# ina.net
KiCad netlist of a schematic drawn in Altium Designer
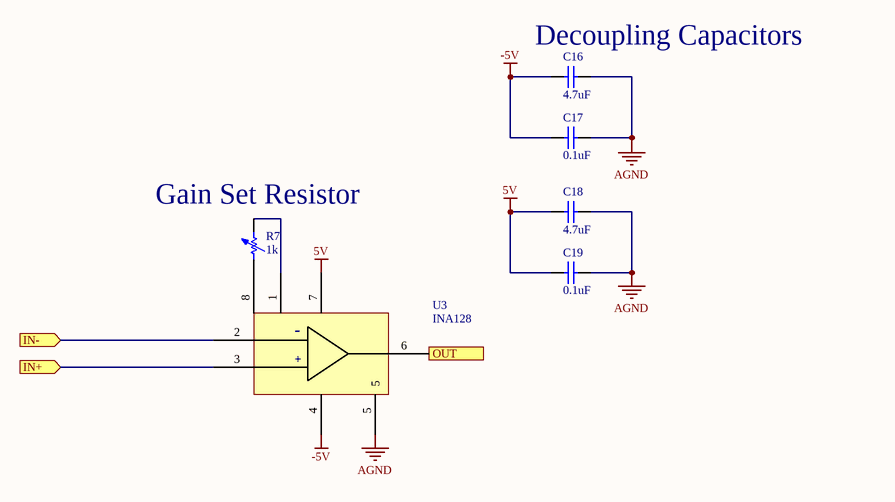
[diagram p0: ina.SchDoc]

(export (version "E")
  (design (tool "Eeschema 10.0.6"))
  (components
    (comp (ref "C16")
      (value "4.7uF")
      (footprint "0402_Cap")
      (description "Capacitor, 4.7uF, 0805")
      (libsource (lib "Arturo_Approved") (part "CL21A475KAQNNNE"))
    )
    (comp (ref "C17")
      (value "0.1uF")
      (footprint "0402_Cap")
      (description "Capacitor, 0.1uF, 0805")
      (libsource (lib "Arturo_Approved") (part "CL21B104KACNNNC"))
    )
    (comp (ref "C18")
      (value "4.7uF")
      (footprint "0402_Cap")
      (description "Capacitor, 4.7uF, 0805")
      (libsource (lib "Arturo_Approved") (part "CL21A475KAQNNNE"))
    )
    (comp (ref "C19")
      (value "0.1uF")
      (footprint "0402_Cap")
      (description "Capacitor, 0.1uF, 0805")
      (libsource (lib "Arturo_Approved") (part "CL21B104KACNNNC"))
    )
    (comp (ref "R7")
      (value "1k")
      (footprint "TRIMRES")
      (description "Variable resistor 1k")
      (libsource (lib "Arturo_Approved") (part "PV36W102C01B00_RES"))
    )
    (comp (ref "U3")
      (value "INA128")
      (footprint "SOIC_8")
      (description "Instrumentation Amp, Generic")
      (libsource (lib "Arturo_Approved") (part "INA128UA/2K5"))
    )
  )
  (nets
    (net (code "1") (name "-5V") (class "Default")
      (node (ref "C16") (pin "1") (pinfunction "1_1") (pintype "passive"))
      (node (ref "C17") (pin "1") (pinfunction "1_1") (pintype "passive"))
      (node (ref "U3") (pin "4") (pintype "passive"))
    )
    (net (code "2") (name "/IN+") (class "Default") (node (ref "U3") (pin "3") (pintype "passive")))
    (net (code "3") (name "/IN-") (class "Default") (node (ref "U3") (pin "2") (pintype "passive")))
    (net (code "4") (name "/OUT") (class "Default") (node (ref "U3") (pin "6") (pintype "passive")))
    (net (code "5") (name "5V") (class "Default")
      (node (ref "C18") (pin "1") (pinfunction "1_1") (pintype "passive"))
      (node (ref "C19") (pin "1") (pinfunction "1_1") (pintype "passive"))
      (node (ref "U3") (pin "7") (pintype "passive"))
    )
    (net (code "6") (name "AGND") (class "Default")
      (node (ref "C16") (pin "2") (pinfunction "2_2") (pintype "passive"))
      (node (ref "C17") (pin "2") (pinfunction "2_2") (pintype "passive"))
      (node (ref "C18") (pin "2") (pinfunction "2_2") (pintype "passive"))
      (node (ref "C19") (pin "2") (pinfunction "2_2") (pintype "passive"))
      (node (ref "U3") (pin "5") (pinfunction "5_5") (pintype "passive"))
    )
    (net (code "7") (name "Net-(R7-Pad1)") (class "Default")
      (node (ref "R7") (pin "1") (pinfunction "1_1") (pintype "passive"))
      (node (ref "U3") (pin "8") (pinfunction "Gain_8") (pintype "passive"))
    )
    (net (code "8") (name "Net-(R7-Pad2)") (class "Default")
      (node (ref "R7") (pin "2") (pinfunction "2_2") (pintype "passive"))
      (node (ref "U3") (pin "1") (pinfunction "Gain_1") (pintype "passive"))
    )
  )
)
